# IRComms.net
KiCad netlist of a schematic drawn in Altium Designer
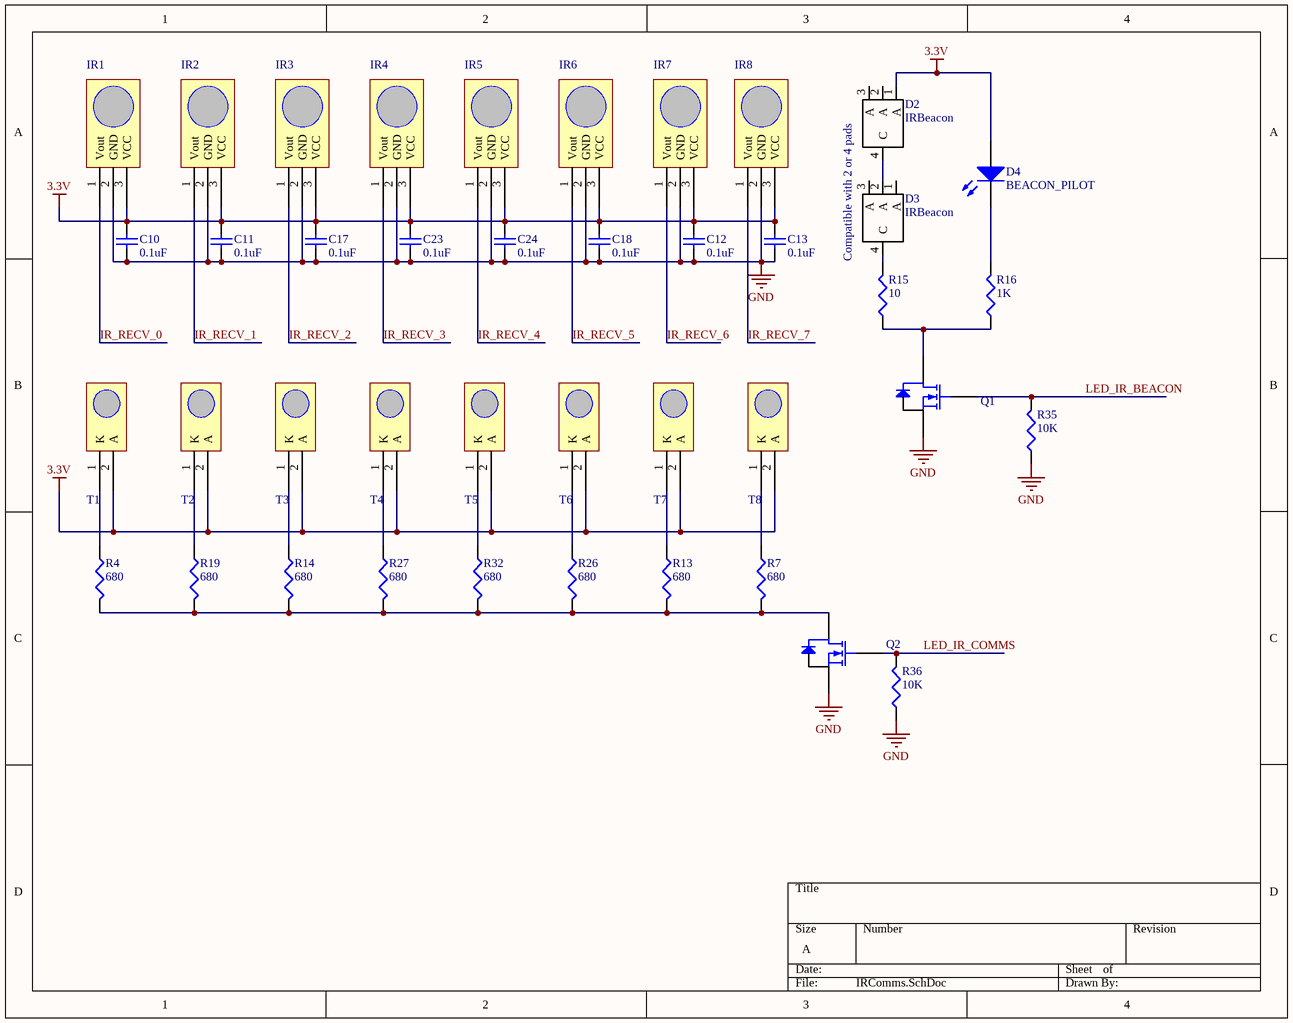
[diagram p0: IRComms.SchDoc]

(export (version "E")
  (design (tool "Eeschema 10.0.6"))
  (components
    (comp (ref "C10")
      (value "0.1uF")
      (footprint "CAPC1005L")
      (description "Capacitor (Semiconductor SIM Model)")
      (fields (field (name "Comment") "Cap Semi") (field (name "PUBLISHER") "Altium Limited"))
      (libsource (lib "Miscellaneous Devices") (part "Cap Semi"))
    )
    (comp (ref "C11")
      (value "0.1uF")
      (footprint "CAPC1005L")
      (description "Capacitor (Semiconductor SIM Model)")
      (fields (field (name "Comment") "Cap Semi") (field (name "PUBLISHER") "Altium Limited"))
      (libsource (lib "Miscellaneous Devices") (part "Cap Semi"))
    )
    (comp (ref "C12")
      (value "0.1uF")
      (footprint "CAPC1005L")
      (description "Capacitor (Semiconductor SIM Model)")
      (fields (field (name "Comment") "Cap Semi") (field (name "PUBLISHER") "Altium Limited"))
      (libsource (lib "Miscellaneous Devices") (part "Cap Semi"))
    )
    (comp (ref "C13")
      (value "0.1uF")
      (footprint "CAPC1005L")
      (description "Capacitor (Semiconductor SIM Model)")
      (fields (field (name "Comment") "Cap Semi") (field (name "PUBLISHER") "Altium Limited"))
      (libsource (lib "Miscellaneous Devices") (part "Cap Semi"))
    )
    (comp (ref "C17")
      (value "0.1uF")
      (footprint "CAPC1005L")
      (description "Capacitor (Semiconductor SIM Model)")
      (fields (field (name "Comment") "Cap Semi") (field (name "PUBLISHER") "Altium Limited"))
      (libsource (lib "Miscellaneous Devices") (part "Cap Semi"))
    )
    (comp (ref "C18")
      (value "0.1uF")
      (footprint "CAPC1005L")
      (description "Capacitor (Semiconductor SIM Model)")
      (fields (field (name "Comment") "Cap Semi") (field (name "PUBLISHER") "Altium Limited"))
      (libsource (lib "Miscellaneous Devices") (part "Cap Semi"))
    )
    (comp (ref "C23")
      (value "0.1uF")
      (footprint "CAPC1005L")
      (description "Capacitor (Semiconductor SIM Model)")
      (fields (field (name "Comment") "Cap Semi") (field (name "PUBLISHER") "Altium Limited"))
      (libsource (lib "Miscellaneous Devices") (part "Cap Semi"))
    )
    (comp (ref "C24")
      (value "0.1uF")
      (footprint "CAPC1005L")
      (description "Capacitor (Semiconductor SIM Model)")
      (fields (field (name "Comment") "Cap Semi") (field (name "PUBLISHER") "Altium Limited"))
      (libsource (lib "Miscellaneous Devices") (part "Cap Semi"))
    )
    (comp (ref "D2") (value "IRBeacon") (footprint "IRBeacon") (libsource (lib "mrone") (part "IRBeacon")))
    (comp (ref "D3") (value "IRBeacon") (footprint "IRBeacon") (libsource (lib "mrone") (part "IRBeacon")))
    (comp (ref "D4")
      (value "BEACON_PILOT")
      (footprint "SurfaceMount(603)")
      (libsource (lib "mrone") (part "LED"))
    )
    (comp (ref "IR1")
      (value "GP1UX31QS")
      (footprint "GP1UX31QS")
      (libsource (lib "mrone") (part "GP1UX31QS"))
    )
    (comp (ref "IR2")
      (value "GP1UX31QS")
      (footprint "GP1UX31QS")
      (libsource (lib "mrone") (part "GP1UX31QS"))
    )
    (comp (ref "IR3")
      (value "GP1UX31QS")
      (footprint "GP1UX31QS")
      (libsource (lib "mrone") (part "GP1UX31QS"))
    )
    (comp (ref "IR4")
      (value "GP1UX31QS")
      (footprint "GP1UX31QS")
      (libsource (lib "mrone") (part "GP1UX31QS"))
    )
    (comp (ref "IR5")
      (value "GP1UX31QS")
      (footprint "GP1UX31QS")
      (libsource (lib "mrone") (part "GP1UX31QS"))
    )
    (comp (ref "IR6")
      (value "GP1UX31QS")
      (footprint "GP1UX31QS")
      (libsource (lib "mrone") (part "GP1UX31QS"))
    )
    (comp (ref "IR7")
      (value "GP1UX31QS")
      (footprint "GP1UX31QS")
      (libsource (lib "mrone") (part "GP1UX31QS"))
    )
    (comp (ref "IR8")
      (value "GP1UX31QS")
      (footprint "GP1UX31QS")
      (libsource (lib "mrone") (part "GP1UX31QS"))
    )
    (comp (ref "Q1") (value "Mosfet") (footprint "SOT-23") (libsource (lib "mrone") (part "Mosfet")))
    (comp (ref "Q2") (value "Mosfet") (footprint "SOT-23") (libsource (lib "mrone") (part "Mosfet")))
    (comp (ref "R4")
      (value "680")
      (footprint "RESC1608L")
      (description "Resistor")
      (fields (field (name "Comment") "Res3") (field (name "PUBLISHER") "Altium Limited"))
      (libsource (lib "Miscellaneous Devices") (part "Res3"))
    )
    (comp (ref "R7")
      (value "680")
      (footprint "RESC1608L")
      (description "Resistor")
      (fields (field (name "Comment") "Res3") (field (name "PUBLISHER") "Altium Limited"))
      (libsource (lib "Miscellaneous Devices") (part "Res3"))
    )
    (comp (ref "R13")
      (value "680")
      (footprint "RESC1608L")
      (description "Resistor")
      (fields (field (name "Comment") "Res3") (field (name "PUBLISHER") "Altium Limited"))
      (libsource (lib "Miscellaneous Devices") (part "Res3"))
    )
    (comp (ref "R14")
      (value "680")
      (footprint "RESC1608L")
      (description "Resistor")
      (fields (field (name "Comment") "Res3") (field (name "PUBLISHER") "Altium Limited"))
      (libsource (lib "Miscellaneous Devices") (part "Res3"))
    )
    (comp (ref "R15")
      (value "10")
      (footprint "RESC1608L")
      (description "Resistor")
      (fields (field (name "Comment") "Res3") (field (name "PUBLISHER") "Altium Limited"))
      (libsource (lib "Miscellaneous Devices") (part "Res3"))
    )
    (comp (ref "R16")
      (value "1K")
      (footprint "RESC1608L")
      (description "Resistor")
      (fields (field (name "Comment") "Res3") (field (name "PUBLISHER") "Altium Limited"))
      (libsource (lib "Miscellaneous Devices") (part "Res3"))
    )
    (comp (ref "R19")
      (value "680")
      (footprint "RESC1608L")
      (description "Resistor")
      (fields (field (name "Comment") "Res3") (field (name "PUBLISHER") "Altium Limited"))
      (libsource (lib "Miscellaneous Devices") (part "Res3"))
    )
    (comp (ref "R26")
      (value "680")
      (footprint "RESC1608L")
      (description "Resistor")
      (fields (field (name "Comment") "Res3") (field (name "PUBLISHER") "Altium Limited"))
      (libsource (lib "Miscellaneous Devices") (part "Res3"))
    )
    (comp (ref "R27")
      (value "680")
      (footprint "RESC1608L")
      (description "Resistor")
      (fields (field (name "Comment") "Res3") (field (name "PUBLISHER") "Altium Limited"))
      (libsource (lib "Miscellaneous Devices") (part "Res3"))
    )
    (comp (ref "R32")
      (value "680")
      (footprint "RESC1608L")
      (description "Resistor")
      (fields (field (name "Comment") "Res3") (field (name "PUBLISHER") "Altium Limited"))
      (libsource (lib "Miscellaneous Devices") (part "Res3"))
    )
    (comp (ref "R35")
      (value "10K")
      (footprint "RESC1608L")
      (description "Resistor")
      (fields (field (name "Comment") "Res3") (field (name "PUBLISHER") "Altium Limited"))
      (libsource (lib "Miscellaneous Devices") (part "Res3"))
    )
    (comp (ref "R36")
      (value "10K")
      (footprint "RESC1608L")
      (description "Resistor")
      (fields (field (name "Comment") "Res3") (field (name "PUBLISHER") "Altium Limited"))
      (libsource (lib "Miscellaneous Devices") (part "Res3"))
    )
    (comp (ref "T1") (value "LN54") (footprint "LN54") (libsource (lib "mrone") (part "LN54")))
    (comp (ref "T2") (value "LN54") (footprint "LN54") (libsource (lib "mrone") (part "LN54")))
    (comp (ref "T3") (value "LN54") (footprint "LN54") (libsource (lib "mrone") (part "LN54")))
    (comp (ref "T4") (value "LN54") (footprint "LN54") (libsource (lib "mrone") (part "LN54")))
    (comp (ref "T5") (value "LN54") (footprint "LN54") (libsource (lib "mrone") (part "LN54")))
    (comp (ref "T6") (value "LN54") (footprint "LN54") (libsource (lib "mrone") (part "LN54")))
    (comp (ref "T7") (value "LN54") (footprint "LN54") (libsource (lib "mrone") (part "LN54")))
    (comp (ref "T8") (value "LN54") (footprint "LN54") (libsource (lib "mrone") (part "LN54")))
  )
  (nets
    (net (code "1") (name "/IR_RECV_0") (class "Default")
      (node (ref "IR1") (pin "1") (pinfunction "Vout_1") (pintype "passive"))
    )
    (net (code "2") (name "/IR_RECV_1") (class "Default")
      (node (ref "IR2") (pin "1") (pinfunction "Vout_1") (pintype "passive"))
    )
    (net (code "3") (name "/IR_RECV_2") (class "Default")
      (node (ref "IR3") (pin "1") (pinfunction "Vout_1") (pintype "passive"))
    )
    (net (code "4") (name "/IR_RECV_3") (class "Default")
      (node (ref "IR4") (pin "1") (pinfunction "Vout_1") (pintype "passive"))
    )
    (net (code "5") (name "/IR_RECV_4") (class "Default")
      (node (ref "IR5") (pin "1") (pinfunction "Vout_1") (pintype "passive"))
    )
    (net (code "6") (name "/IR_RECV_5") (class "Default")
      (node (ref "IR6") (pin "1") (pinfunction "Vout_1") (pintype "passive"))
    )
    (net (code "7") (name "/IR_RECV_6") (class "Default")
      (node (ref "IR7") (pin "1") (pinfunction "Vout_1") (pintype "passive"))
    )
    (net (code "8") (name "/IR_RECV_7") (class "Default")
      (node (ref "IR8") (pin "1") (pinfunction "Vout_1") (pintype "passive"))
    )
    (net (code "9") (name "/LED_IR_BEACON") (class "Default")
      (node (ref "Q1") (pin "1") (pinfunction "G_1") (pintype "passive"))
      (node (ref "R35") (pin "2") (pinfunction "2_2") (pintype "passive"))
    )
    (net (code "10") (name "/LED_IR_COMMS") (class "Default")
      (node (ref "Q2") (pin "1") (pinfunction "G_1") (pintype "passive"))
      (node (ref "R36") (pin "2") (pinfunction "2_2") (pintype "passive"))
    )
    (net (code "11") (name "3.3V") (class "Default")
      (node (ref "C10") (pin "2") (pinfunction "2_2") (pintype "passive"))
      (node (ref "C11") (pin "2") (pinfunction "2_2") (pintype "passive"))
      (node (ref "C12") (pin "2") (pinfunction "2_2") (pintype "passive"))
      (node (ref "C13") (pin "2") (pinfunction "2_2") (pintype "passive"))
      (node (ref "C17") (pin "2") (pinfunction "2_2") (pintype "passive"))
      (node (ref "C18") (pin "2") (pinfunction "2_2") (pintype "passive"))
      (node (ref "C23") (pin "2") (pinfunction "2_2") (pintype "passive"))
      (node (ref "C24") (pin "2") (pinfunction "2_2") (pintype "passive"))
      (node (ref "D2") (pin "1") (pinfunction "A_1") (pintype "passive"))
      (node (ref "D4") (pin "1") (pinfunction "A_1") (pintype "passive"))
      (node (ref "IR1") (pin "3") (pinfunction "VCC_3") (pintype "power_in"))
      (node (ref "IR2") (pin "3") (pinfunction "VCC_3") (pintype "power_in"))
      (node (ref "IR3") (pin "3") (pinfunction "VCC_3") (pintype "power_in"))
      (node (ref "IR4") (pin "3") (pinfunction "VCC_3") (pintype "power_in"))
      (node (ref "IR5") (pin "3") (pinfunction "VCC_3") (pintype "power_in"))
      (node (ref "IR6") (pin "3") (pinfunction "VCC_3") (pintype "power_in"))
      (node (ref "IR7") (pin "3") (pinfunction "VCC_3") (pintype "power_in"))
      (node (ref "IR8") (pin "3") (pinfunction "VCC_3") (pintype "power_in"))
      (node (ref "T1") (pin "2") (pinfunction "A_2") (pintype "passive"))
      (node (ref "T2") (pin "2") (pinfunction "A_2") (pintype "passive"))
      (node (ref "T3") (pin "2") (pinfunction "A_2") (pintype "passive"))
      (node (ref "T4") (pin "2") (pinfunction "A_2") (pintype "passive"))
      (node (ref "T5") (pin "2") (pinfunction "A_2") (pintype "passive"))
      (node (ref "T6") (pin "2") (pinfunction "A_2") (pintype "passive"))
      (node (ref "T7") (pin "2") (pinfunction "A_2") (pintype "passive"))
      (node (ref "T8") (pin "2") (pinfunction "A_2") (pintype "passive"))
    )
    (net (code "12") (name "GND") (class "Default")
      (node (ref "C10") (pin "1") (pinfunction "1_1") (pintype "passive"))
      (node (ref "C11") (pin "1") (pinfunction "1_1") (pintype "passive"))
      (node (ref "C12") (pin "1") (pinfunction "1_1") (pintype "passive"))
      (node (ref "C13") (pin "1") (pinfunction "1_1") (pintype "passive"))
      (node (ref "C17") (pin "1") (pinfunction "1_1") (pintype "passive"))
      (node (ref "C18") (pin "1") (pinfunction "1_1") (pintype "passive"))
      (node (ref "C23") (pin "1") (pinfunction "1_1") (pintype "passive"))
      (node (ref "C24") (pin "1") (pinfunction "1_1") (pintype "passive"))
      (node (ref "IR1") (pin "2") (pinfunction "GND_2") (pintype "power_in"))
      (node (ref "IR2") (pin "2") (pinfunction "GND_2") (pintype "power_in"))
      (node (ref "IR3") (pin "2") (pinfunction "GND_2") (pintype "power_in"))
      (node (ref "IR4") (pin "2") (pinfunction "GND_2") (pintype "power_in"))
      (node (ref "IR5") (pin "2") (pinfunction "GND_2") (pintype "power_in"))
      (node (ref "IR6") (pin "2") (pinfunction "GND_2") (pintype "power_in"))
      (node (ref "IR7") (pin "2") (pinfunction "GND_2") (pintype "power_in"))
      (node (ref "IR8") (pin "2") (pinfunction "GND_2") (pintype "power_in"))
      (node (ref "Q1") (pin "2") (pinfunction "S_2") (pintype "passive"))
      (node (ref "Q2") (pin "2") (pinfunction "S_2") (pintype "passive"))
      (node (ref "R35") (pin "1") (pinfunction "1_1") (pintype "passive"))
      (node (ref "R36") (pin "1") (pinfunction "1_1") (pintype "passive"))
    )
    (net (code "13") (name "Net-(D2-C)") (class "Default")
      (node (ref "D2") (pin "4") (pinfunction "C_4") (pintype "passive"))
      (node (ref "D3") (pin "2") (pinfunction "A_2") (pintype "passive"))
    )
    (net (code "14") (name "Net-(D3-C)") (class "Default")
      (node (ref "D3") (pin "4") (pinfunction "C_4") (pintype "passive"))
      (node (ref "R15") (pin "2") (pinfunction "2_2") (pintype "passive"))
    )
    (net (code "15") (name "Net-(D4-K)") (class "Default")
      (node (ref "D4") (pin "2") (pinfunction "K_2") (pintype "passive"))
      (node (ref "R16") (pin "2") (pinfunction "2_2") (pintype "passive"))
    )
    (net (code "16") (name "Net-(Q1-D)") (class "Default")
      (node (ref "Q1") (pin "3") (pinfunction "D_3") (pintype "passive"))
      (node (ref "R15") (pin "1") (pinfunction "1_1") (pintype "passive"))
      (node (ref "R16") (pin "1") (pinfunction "1_1") (pintype "passive"))
    )
    (net (code "17") (name "Net-(Q2-D)") (class "Default")
      (node (ref "Q2") (pin "3") (pinfunction "D_3") (pintype "passive"))
      (node (ref "R13") (pin "2") (pinfunction "2_2") (pintype "passive"))
      (node (ref "R14") (pin "2") (pinfunction "2_2") (pintype "passive"))
      (node (ref "R19") (pin "2") (pinfunction "2_2") (pintype "passive"))
      (node (ref "R26") (pin "2") (pinfunction "2_2") (pintype "passive"))
      (node (ref "R27") (pin "2") (pinfunction "2_2") (pintype "passive"))
      (node (ref "R32") (pin "2") (pinfunction "2_2") (pintype "passive"))
      (node (ref "R4") (pin "2") (pinfunction "2_2") (pintype "passive"))
      (node (ref "R7") (pin "2") (pinfunction "2_2") (pintype "passive"))
    )
    (net (code "18") (name "Net-(T1-K)") (class "Default")
      (node (ref "R4") (pin "1") (pinfunction "1_1") (pintype "passive"))
      (node (ref "T1") (pin "1") (pinfunction "K_1") (pintype "passive"))
    )
    (net (code "19") (name "Net-(T2-K)") (class "Default")
      (node (ref "R19") (pin "1") (pinfunction "1_1") (pintype "passive"))
      (node (ref "T2") (pin "1") (pinfunction "K_1") (pintype "passive"))
    )
    (net (code "20") (name "Net-(T3-K)") (class "Default")
      (node (ref "R14") (pin "1") (pinfunction "1_1") (pintype "passive"))
      (node (ref "T3") (pin "1") (pinfunction "K_1") (pintype "passive"))
    )
    (net (code "21") (name "Net-(T4-K)") (class "Default")
      (node (ref "R27") (pin "1") (pinfunction "1_1") (pintype "passive"))
      (node (ref "T4") (pin "1") (pinfunction "K_1") (pintype "passive"))
    )
    (net (code "22") (name "Net-(T5-K)") (class "Default")
      (node (ref "R32") (pin "1") (pinfunction "1_1") (pintype "passive"))
      (node (ref "T5") (pin "1") (pinfunction "K_1") (pintype "passive"))
    )
    (net (code "23") (name "Net-(T6-K)") (class "Default")
      (node (ref "R26") (pin "1") (pinfunction "1_1") (pintype "passive"))
      (node (ref "T6") (pin "1") (pinfunction "K_1") (pintype "passive"))
    )
    (net (code "24") (name "Net-(T7-K)") (class "Default")
      (node (ref "R13") (pin "1") (pinfunction "1_1") (pintype "passive"))
      (node (ref "T7") (pin "1") (pinfunction "K_1") (pintype "passive"))
    )
    (net (code "25") (name "Net-(T8-K)") (class "Default")
      (node (ref "R7") (pin "1") (pinfunction "1_1") (pintype "passive"))
      (node (ref "T8") (pin "1") (pinfunction "K_1") (pintype "passive"))
    )
    (net (code "26") (name "unconnected-(D2-A-Pad2)") (class "Default")
      (node (ref "D2") (pin "2") (pinfunction "A_2") (pintype "passive"))
    )
    (net (code "27") (name "unconnected-(D2-A-Pad3)") (class "Default")
      (node (ref "D2") (pin "3") (pinfunction "A_3") (pintype "passive"))
    )
    (net (code "28") (name "unconnected-(D3-A-Pad1)") (class "Default")
      (node (ref "D3") (pin "1") (pinfunction "A_1") (pintype "passive"))
    )
    (net (code "29") (name "unconnected-(D3-A-Pad3)") (class "Default")
      (node (ref "D3") (pin "3") (pinfunction "A_3") (pintype "passive"))
    )
  )
)
